# IIM-42652_breakout.net
KiCad netlist of a schematic drawn in Altium Designer
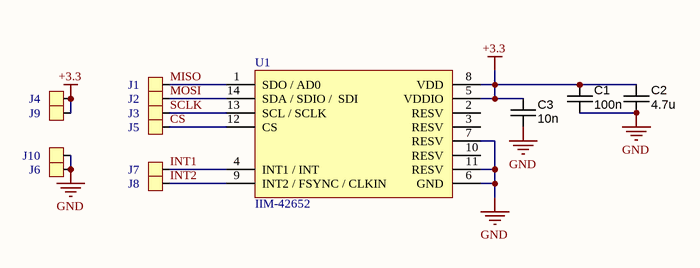
[diagram p0: IIM-42652_breakout.SchDoc]

(export (version "E")
  (design (tool "Eeschema 10.0.6"))
  (components
    (comp (ref "C1")
      (value "100n")
      (footprint "CAPC1005X55N")
      (description "Capacitor SMD Cer 100nF 10% 16V X5R 0402")
      (fields (field (name "TOLERANCE") "±10%"))
      (libsource (lib "PBL - Capacitors") (part "CAPC_100n_0402_X5R_16V_10%"))
    )
    (comp (ref "C2")
      (value "4.7u")
      (footprint "CAPC1608X90N")
      (description "Capacitor SMD Cer 2.2uF 10% 10V X5R 0603")
      (fields (field (name "TOLERANCE") "±10%") (field (name "Comment") "approved sub OK"))
      (libsource (lib "PBL - Capacitors") (part "CAPC_2u2_0603_10V_10%"))
    )
    (comp (ref "C3")
      (value "10n")
      (footprint "CAPC1005X55N")
      (description "Capacitor SMD Cer 10nF 10% 16V X7R 0402")
      (fields (field (name "TOLERANCE") "±10%"))
      (libsource (lib "PBL - Capacitors") (part "CAPC_10n_0402_X7R_16V_10%"))
    )
    (comp (ref "J1") (value "MISO") (footprint "PAD-1020") (libsource (lib "connectors") (part "SOLDER-PAD")))
    (comp (ref "J2") (value "MOSI") (footprint "PAD-1020") (libsource (lib "connectors") (part "SOLDER-PAD")))
    (comp (ref "J3") (value "SCLK") (footprint "PAD-1020") (libsource (lib "connectors") (part "SOLDER-PAD")))
    (comp (ref "J4") (value "+3.3") (footprint "PAD-1020") (libsource (lib "connectors") (part "SOLDER-PAD")))
    (comp (ref "J5") (value "CS") (footprint "PAD-1020") (libsource (lib "connectors") (part "SOLDER-PAD")))
    (comp (ref "J6") (value "GND") (footprint "PAD-1020") (libsource (lib "connectors") (part "SOLDER-PAD")))
    (comp (ref "J7") (value "INT1") (footprint "PAD-1020") (libsource (lib "connectors") (part "SOLDER-PAD")))
    (comp (ref "J8") (value "INT2") (footprint "PAD-1020") (libsource (lib "connectors") (part "SOLDER-PAD")))
    (comp (ref "J9") (value "+3.3") (footprint "PAD-1020") (libsource (lib "connectors") (part "SOLDER-PAD")))
    (comp (ref "J10") (value "GND") (footprint "PAD-1020") (libsource (lib "connectors") (part "SOLDER-PAD")))
    (comp (ref "U1")
      (value "IIM-42652")
      (footprint "IIM-42652_LGA14")
      (libsource (lib "digital") (part "IIM-42652"))
    )
  )
  (nets
    (net (code "1") (name "+3.3") (class "Default")
      (node (ref "C1") (pin "1") (pintype "passive"))
      (node (ref "C2") (pin "1") (pintype "passive"))
      (node (ref "C3") (pin "1") (pintype "passive"))
      (node (ref "J4") (pin "1") (pinfunction "1_1") (pintype "passive"))
      (node (ref "J9") (pin "1") (pinfunction "1_1") (pintype "passive"))
      (node (ref "U1") (pin "5") (pinfunction "VDDIO_5") (pintype "passive"))
      (node (ref "U1") (pin "8") (pinfunction "VDD_8") (pintype "passive"))
    )
    (net (code "2") (name "/CS") (class "Default")
      (node (ref "J5") (pin "1") (pinfunction "1_1") (pintype "passive"))
      (node (ref "U1") (pin "12") (pinfunction "CS_12") (pintype "passive"))
    )
    (net (code "3") (name "/INT1") (class "Default")
      (node (ref "J7") (pin "1") (pinfunction "1_1") (pintype "passive"))
      (node (ref "U1") (pin "4") (pinfunction "INT1_/_INT_4") (pintype "passive"))
    )
    (net (code "4") (name "/INT2") (class "Default")
      (node (ref "J8") (pin "1") (pinfunction "1_1") (pintype "passive"))
      (node (ref "U1") (pin "9") (pinfunction "INT2_/_FSYNC_/_CLKIN_9") (pintype "passive"))
    )
    (net (code "5") (name "/MISO") (class "Default")
      (node (ref "J1") (pin "1") (pinfunction "1_1") (pintype "passive"))
      (node (ref "U1") (pin "1") (pinfunction "SDO_/_AD0_1") (pintype "passive"))
    )
    (net (code "6") (name "/MOSI") (class "Default")
      (node (ref "J2") (pin "1") (pinfunction "1_1") (pintype "passive"))
      (node (ref "U1") (pin "14") (pinfunction "SDA_/_SDIO_/__SDI_14") (pintype "passive"))
    )
    (net (code "7") (name "/SCLK") (class "Default")
      (node (ref "J3") (pin "1") (pinfunction "1_1") (pintype "passive"))
      (node (ref "U1") (pin "13") (pinfunction "SCL_/_SCLK_13") (pintype "passive"))
    )
    (net (code "8") (name "GND") (class "Default")
      (node (ref "C1") (pin "2") (pintype "passive"))
      (node (ref "C2") (pin "2") (pintype "passive"))
      (node (ref "C3") (pin "2") (pintype "passive"))
      (node (ref "J10") (pin "1") (pinfunction "1_1") (pintype "passive"))
      (node (ref "J6") (pin "1") (pinfunction "1_1") (pintype "passive"))
      (node (ref "U1") (pin "11") (pinfunction "RESV_11") (pintype "passive"))
      (node (ref "U1") (pin "6") (pinfunction "GND_6") (pintype "passive"))
      (node (ref "U1") (pin "7") (pinfunction "RESV_7") (pintype "passive"))
    )
    (net (code "9") (name "unconnected-(U1-RESV-Pad2)") (class "Default")
      (node (ref "U1") (pin "2") (pinfunction "RESV_2") (pintype "passive"))
    )
    (net (code "10") (name "unconnected-(U1-RESV-Pad3)") (class "Default")
      (node (ref "U1") (pin "3") (pinfunction "RESV_3") (pintype "passive"))
    )
    (net (code "11") (name "unconnected-(U1-RESV-Pad10)") (class "Default")
      (node (ref "U1") (pin "10") (pinfunction "RESV_10") (pintype "passive"))
    )
  )
)
